# p128necontrol.net
KiCad netlist of a schematic drawn in EAGLE
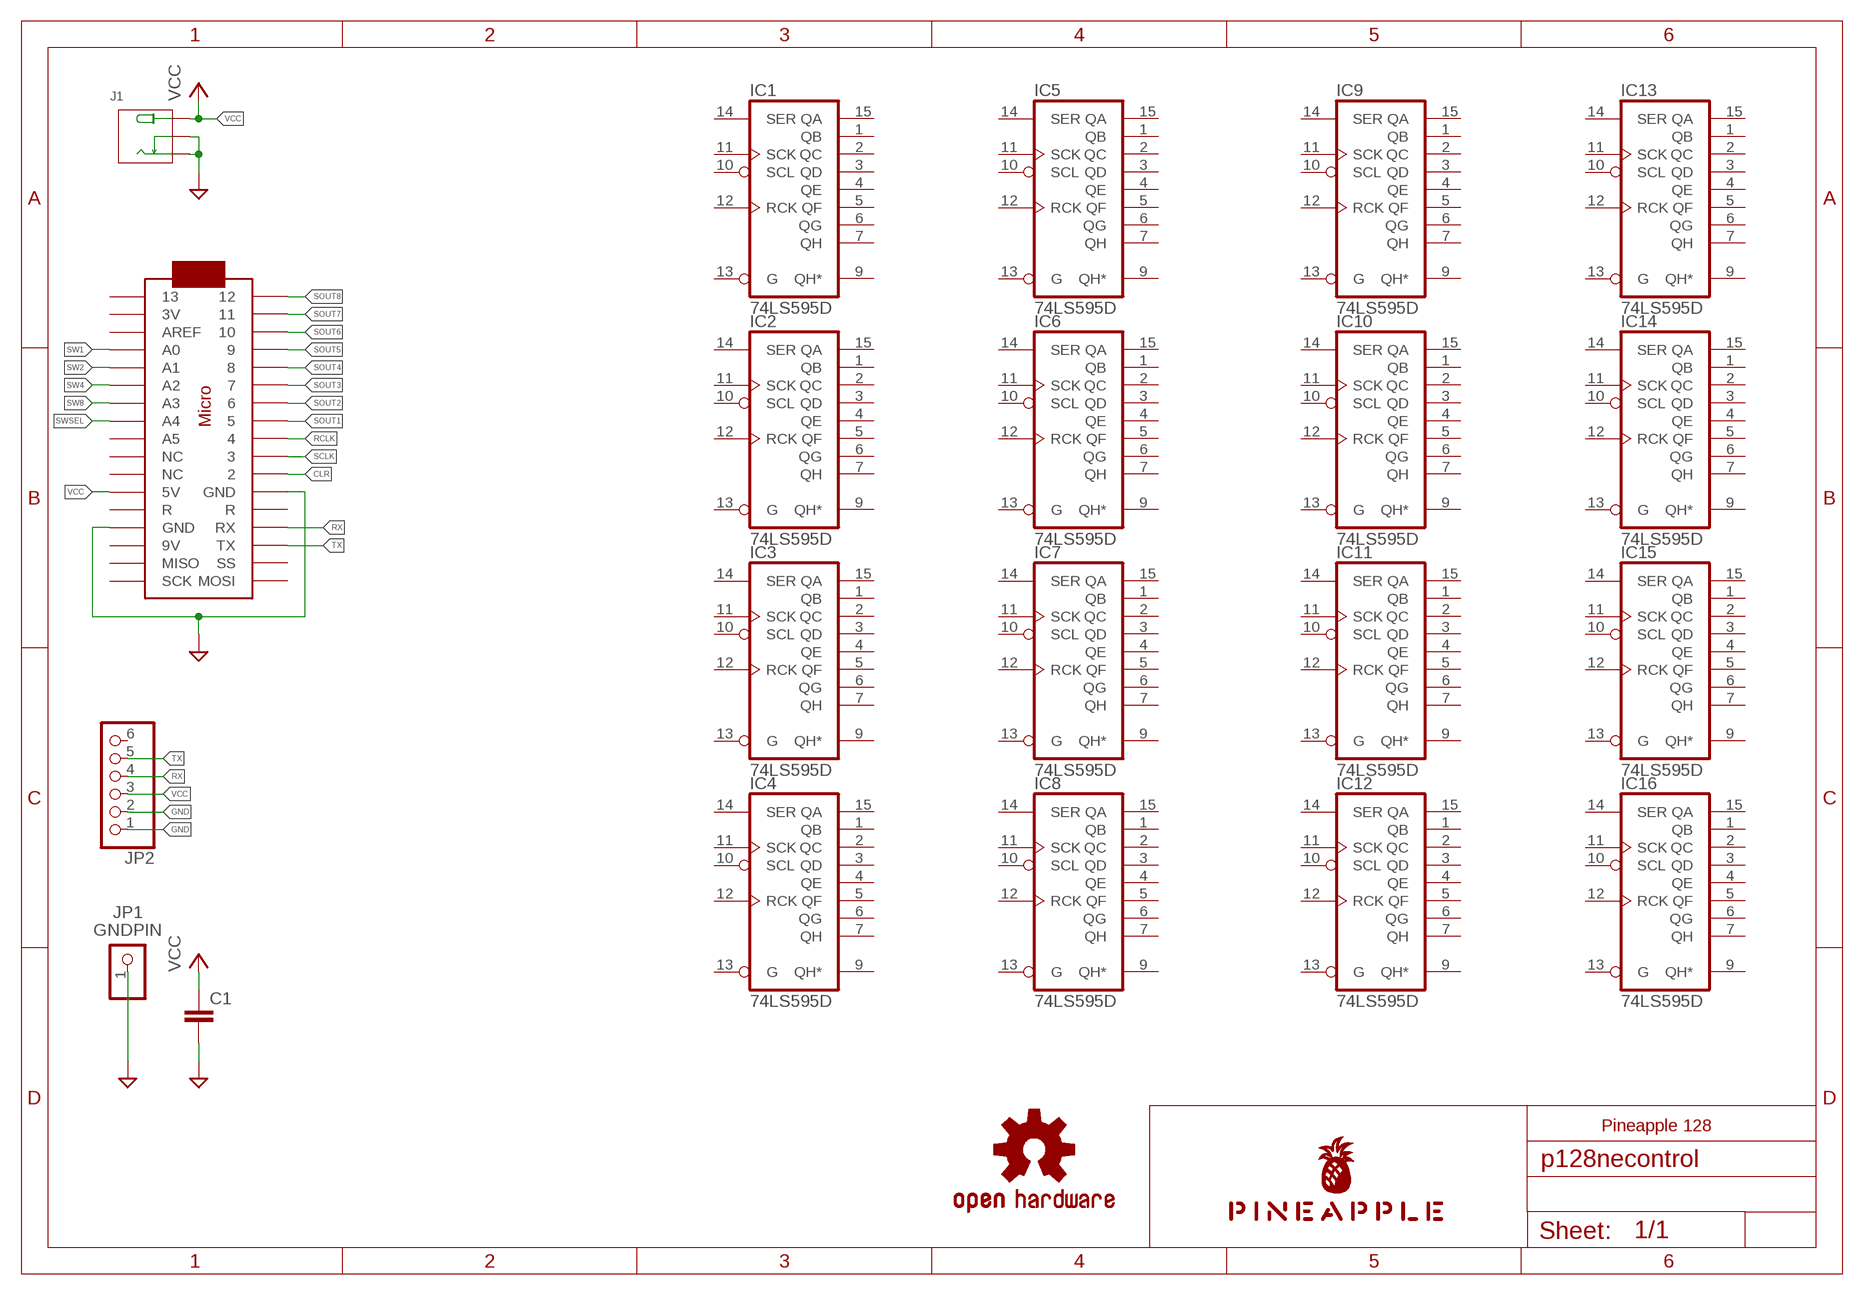
[diagram p0: schematic, sheet 1]

(export (version "E")
  (design (tool "Eeschema 10.0.6"))
  (components
    (comp (ref "C1")
      (value "C-EU025-024X044")
      (footprint "eagle-import:C025-024X044")
      (libsource (lib "eagle-import") (part "C-EU025-024X044"))
    )
    (comp (ref "IC1")
      (value "74LS595D")
      (footprint "eagle-import:SO16")
      (libsource (lib "eagle-import") (part "74595DLS"))
    )
    (comp (ref "IC2")
      (value "74LS595D")
      (footprint "eagle-import:SO16")
      (libsource (lib "eagle-import") (part "74595DLS"))
    )
    (comp (ref "IC3")
      (value "74LS595D")
      (footprint "eagle-import:SO16")
      (libsource (lib "eagle-import") (part "74595DLS"))
    )
    (comp (ref "IC4")
      (value "74LS595D")
      (footprint "eagle-import:SO16")
      (libsource (lib "eagle-import") (part "74595DLS"))
    )
    (comp (ref "IC5")
      (value "74LS595D")
      (footprint "eagle-import:SO16")
      (libsource (lib "eagle-import") (part "74595DLS"))
    )
    (comp (ref "IC6")
      (value "74LS595D")
      (footprint "eagle-import:SO16")
      (libsource (lib "eagle-import") (part "74595DLS"))
    )
    (comp (ref "IC7")
      (value "74LS595D")
      (footprint "eagle-import:SO16")
      (libsource (lib "eagle-import") (part "74595DLS"))
    )
    (comp (ref "IC8")
      (value "74LS595D")
      (footprint "eagle-import:SO16")
      (libsource (lib "eagle-import") (part "74595DLS"))
    )
    (comp (ref "IC9")
      (value "74LS595D")
      (footprint "eagle-import:SO16")
      (libsource (lib "eagle-import") (part "74595DLS"))
    )
    (comp (ref "IC10")
      (value "74LS595D")
      (footprint "eagle-import:SO16")
      (libsource (lib "eagle-import") (part "74595DLS"))
    )
    (comp (ref "IC11")
      (value "74LS595D")
      (footprint "eagle-import:SO16")
      (libsource (lib "eagle-import") (part "74595DLS"))
    )
    (comp (ref "IC12")
      (value "74LS595D")
      (footprint "eagle-import:SO16")
      (libsource (lib "eagle-import") (part "74595DLS"))
    )
    (comp (ref "IC13")
      (value "74LS595D")
      (footprint "eagle-import:SO16")
      (libsource (lib "eagle-import") (part "74595DLS"))
    )
    (comp (ref "IC14")
      (value "74LS595D")
      (footprint "eagle-import:SO16")
      (libsource (lib "eagle-import") (part "74595DLS"))
    )
    (comp (ref "IC15")
      (value "74LS595D")
      (footprint "eagle-import:SO16")
      (libsource (lib "eagle-import") (part "74595DLS"))
    )
    (comp (ref "IC16")
      (value "74LS595D")
      (footprint "eagle-import:SO16")
      (libsource (lib "eagle-import") (part "74595DLS"))
    )
    (comp (ref "J1")
      (value "JACK-DC-005'DC-005'")
      (footprint "eagle-import:3P-L14.2_W11.0_H9.0MM")
      (libsource (lib "eagle-import") (part "JACK-DC-005'DC-005'"))
    )
    (comp (ref "JP1")
      (value "GNDPIN")
      (footprint "eagle-import:1X01")
      (libsource (lib "eagle-import") (part "PINHD-1X1"))
    )
    (comp (ref "JP2")
      (value "PINHD-1X6")
      (footprint "eagle-import:1X06")
      (libsource (lib "eagle-import") (part "PINHD-1X6"))
    )
    (comp (ref "LOGO1")
      (value "OSHW-LOGOS-COPPER")
      (footprint "eagle-import:OSHW-LOGO-S_COPPER")
      (libsource (lib "eagle-import") (part "OSHW-LOGOS-COPPER"))
    )
    (comp (ref "U$1")
      (value "PINEAPPLE450_SILK")
      (footprint "eagle-import:PINEAPPLE450_SILK")
      (libsource (lib "eagle-import") (part "PINEAPPLE450_SILK"))
    )
    (comp (ref "U$2")
      (value "ARDUINOMICRO")
      (footprint "eagle-import:ARDUINOMICRO")
      (libsource (lib "eagle-import") (part "ARDUINOMICRO"))
    )
  )
  (nets
    (net (code "1") (name "CLR") (class "Default")
      (node (ref "U$2") (pin "P$11") (pinfunction "2_P$11") (pintype "bidirectional"))
    )
    (net (code "2") (name "GND") (class "Default")
      (node (ref "C1") (pin "2") (pinfunction "2_2") (pintype "passive"))
      (node (ref "J1") (pin "-1") (pinfunction "-_-1") (pintype "bidirectional"))
      (node (ref "J1") (pin "-2") (pinfunction "CDN_-2") (pintype "bidirectional"))
      (node (ref "JP1") (pin "1") (pinfunction "1_1") (pintype "passive"))
      (node (ref "JP2") (pin "1") (pinfunction "1_1") (pintype "passive"))
      (node (ref "JP2") (pin "2") (pinfunction "2_2") (pintype "passive"))
      (node (ref "U$2") (pin "P$12") (pinfunction "GND_P$12") (pintype "bidirectional"))
      (node (ref "U$2") (pin "P$21") (pinfunction "GND_P$21") (pintype "bidirectional"))
    )
    (net (code "3") (name "RCLK") (class "Default")
      (node (ref "U$2") (pin "P$9") (pinfunction "4_P$9") (pintype "bidirectional"))
    )
    (net (code "4") (name "RX") (class "Default")
      (node (ref "JP2") (pin "4") (pinfunction "4_4") (pintype "passive"))
      (node (ref "U$2") (pin "P$14") (pinfunction "RX_P$14") (pintype "bidirectional"))
    )
    (net (code "5") (name "SCLK") (class "Default")
      (node (ref "U$2") (pin "P$10") (pinfunction "3_P$10") (pintype "bidirectional"))
    )
    (net (code "6") (name "SOUT1") (class "Default")
      (node (ref "U$2") (pin "P$8") (pinfunction "5_P$8") (pintype "bidirectional"))
    )
    (net (code "7") (name "SOUT2") (class "Default")
      (node (ref "U$2") (pin "P$7") (pinfunction "6_P$7") (pintype "bidirectional"))
    )
    (net (code "8") (name "SOUT3") (class "Default")
      (node (ref "U$2") (pin "P$6") (pinfunction "7_P$6") (pintype "bidirectional"))
    )
    (net (code "9") (name "SOUT4") (class "Default")
      (node (ref "U$2") (pin "P$5") (pinfunction "8_P$5") (pintype "bidirectional"))
    )
    (net (code "10") (name "SOUT5") (class "Default")
      (node (ref "U$2") (pin "P$4") (pinfunction "9_P$4") (pintype "bidirectional"))
    )
    (net (code "11") (name "SOUT6") (class "Default")
      (node (ref "U$2") (pin "P$3") (pinfunction "10_P$3") (pintype "bidirectional"))
    )
    (net (code "12") (name "SOUT7") (class "Default")
      (node (ref "U$2") (pin "P$2") (pinfunction "11_P$2") (pintype "bidirectional"))
    )
    (net (code "13") (name "SOUT8") (class "Default")
      (node (ref "U$2") (pin "P$1") (pinfunction "12_P$1") (pintype "bidirectional"))
    )
    (net (code "14") (name "SW1") (class "Default")
      (node (ref "U$2") (pin "P$31") (pinfunction "A0_P$31") (pintype "bidirectional"))
    )
    (net (code "15") (name "SW2") (class "Default")
      (node (ref "U$2") (pin "P$30") (pinfunction "A1_P$30") (pintype "bidirectional"))
    )
    (net (code "16") (name "SW4") (class "Default")
      (node (ref "U$2") (pin "P$29") (pinfunction "A2_P$29") (pintype "bidirectional"))
    )
    (net (code "17") (name "SW8") (class "Default")
      (node (ref "U$2") (pin "P$28") (pinfunction "A3_P$28") (pintype "bidirectional"))
    )
    (net (code "18") (name "SWSEL") (class "Default")
      (node (ref "U$2") (pin "P$27") (pinfunction "A4_P$27") (pintype "bidirectional"))
    )
    (net (code "19") (name "TX") (class "Default")
      (node (ref "JP2") (pin "5") (pinfunction "5_5") (pintype "passive"))
      (node (ref "U$2") (pin "P$15") (pinfunction "TX_P$15") (pintype "bidirectional"))
    )
    (net (code "20") (name "VCC") (class "Default")
      (node (ref "C1") (pin "1") (pinfunction "1_1") (pintype "passive"))
      (node (ref "J1") (pin "+") (pinfunction "+_+") (pintype "bidirectional"))
      (node (ref "JP2") (pin "3") (pinfunction "3_3") (pintype "passive"))
      (node (ref "U$2") (pin "P$23") (pinfunction "5V_P$23") (pintype "bidirectional"))
    )
    (net (code "21") (name "unconnected-(IC1A-G-Pad13)") (class "Default")
      (node (ref "IC1") (pin "13") (pinfunction "G_13") (pintype "input"))
    )
    (net (code "22") (name "unconnected-(IC1A-QA-Pad15)") (class "Default")
      (node (ref "IC1") (pin "15") (pinfunction "QA_15") (pintype "tri_state"))
    )
    (net (code "23") (name "unconnected-(IC1A-QB-Pad1)") (class "Default")
      (node (ref "IC1") (pin "1") (pinfunction "QB_1") (pintype "tri_state"))
    )
    (net (code "24") (name "unconnected-(IC1A-QC-Pad2)") (class "Default")
      (node (ref "IC1") (pin "2") (pinfunction "QC_2") (pintype "tri_state"))
    )
    (net (code "25") (name "unconnected-(IC1A-QD-Pad3)") (class "Default")
      (node (ref "IC1") (pin "3") (pinfunction "QD_3") (pintype "tri_state"))
    )
    (net (code "26") (name "unconnected-(IC1A-QE-Pad4)") (class "Default")
      (node (ref "IC1") (pin "4") (pinfunction "QE_4") (pintype "tri_state"))
    )
    (net (code "27") (name "unconnected-(IC1A-QF-Pad5)") (class "Default")
      (node (ref "IC1") (pin "5") (pinfunction "QF_5") (pintype "tri_state"))
    )
    (net (code "28") (name "unconnected-(IC1A-QG-Pad6)") (class "Default")
      (node (ref "IC1") (pin "6") (pinfunction "QG_6") (pintype "tri_state"))
    )
    (net (code "29") (name "unconnected-(IC1A-QH*-Pad9)") (class "Default")
      (node (ref "IC1") (pin "9") (pinfunction "QH*_9") (pintype "tri_state"))
    )
    (net (code "30") (name "unconnected-(IC1A-QH-Pad7)") (class "Default")
      (node (ref "IC1") (pin "7") (pinfunction "QH_7") (pintype "tri_state"))
    )
    (net (code "31") (name "unconnected-(IC1A-RCK-Pad12)") (class "Default")
      (node (ref "IC1") (pin "12") (pinfunction "RCK_12") (pintype "input"))
    )
    (net (code "32") (name "unconnected-(IC1A-SCK-Pad11)") (class "Default")
      (node (ref "IC1") (pin "11") (pinfunction "SCK_11") (pintype "input"))
    )
    (net (code "33") (name "unconnected-(IC1A-SCL-Pad10)") (class "Default")
      (node (ref "IC1") (pin "10") (pinfunction "SCL_10") (pintype "input"))
    )
    (net (code "34") (name "unconnected-(IC1A-SER-Pad14)") (class "Default")
      (node (ref "IC1") (pin "14") (pinfunction "SER_14") (pintype "input"))
    )
    (net (code "35") (name "unconnected-(IC2A-G-Pad13)") (class "Default")
      (node (ref "IC2") (pin "13") (pinfunction "G_13") (pintype "input"))
    )
    (net (code "36") (name "unconnected-(IC2A-QA-Pad15)") (class "Default")
      (node (ref "IC2") (pin "15") (pinfunction "QA_15") (pintype "tri_state"))
    )
    (net (code "37") (name "unconnected-(IC2A-QB-Pad1)") (class "Default")
      (node (ref "IC2") (pin "1") (pinfunction "QB_1") (pintype "tri_state"))
    )
    (net (code "38") (name "unconnected-(IC2A-QC-Pad2)") (class "Default")
      (node (ref "IC2") (pin "2") (pinfunction "QC_2") (pintype "tri_state"))
    )
    (net (code "39") (name "unconnected-(IC2A-QD-Pad3)") (class "Default")
      (node (ref "IC2") (pin "3") (pinfunction "QD_3") (pintype "tri_state"))
    )
    (net (code "40") (name "unconnected-(IC2A-QE-Pad4)") (class "Default")
      (node (ref "IC2") (pin "4") (pinfunction "QE_4") (pintype "tri_state"))
    )
    (net (code "41") (name "unconnected-(IC2A-QF-Pad5)") (class "Default")
      (node (ref "IC2") (pin "5") (pinfunction "QF_5") (pintype "tri_state"))
    )
    (net (code "42") (name "unconnected-(IC2A-QG-Pad6)") (class "Default")
      (node (ref "IC2") (pin "6") (pinfunction "QG_6") (pintype "tri_state"))
    )
    (net (code "43") (name "unconnected-(IC2A-QH*-Pad9)") (class "Default")
      (node (ref "IC2") (pin "9") (pinfunction "QH*_9") (pintype "tri_state"))
    )
    (net (code "44") (name "unconnected-(IC2A-QH-Pad7)") (class "Default")
      (node (ref "IC2") (pin "7") (pinfunction "QH_7") (pintype "tri_state"))
    )
    (net (code "45") (name "unconnected-(IC2A-RCK-Pad12)") (class "Default")
      (node (ref "IC2") (pin "12") (pinfunction "RCK_12") (pintype "input"))
    )
    (net (code "46") (name "unconnected-(IC2A-SCK-Pad11)") (class "Default")
      (node (ref "IC2") (pin "11") (pinfunction "SCK_11") (pintype "input"))
    )
    (net (code "47") (name "unconnected-(IC2A-SCL-Pad10)") (class "Default")
      (node (ref "IC2") (pin "10") (pinfunction "SCL_10") (pintype "input"))
    )
    (net (code "48") (name "unconnected-(IC2A-SER-Pad14)") (class "Default")
      (node (ref "IC2") (pin "14") (pinfunction "SER_14") (pintype "input"))
    )
    (net (code "49") (name "unconnected-(IC3A-G-Pad13)") (class "Default")
      (node (ref "IC3") (pin "13") (pinfunction "G_13") (pintype "input"))
    )
    (net (code "50") (name "unconnected-(IC3A-QA-Pad15)") (class "Default")
      (node (ref "IC3") (pin "15") (pinfunction "QA_15") (pintype "tri_state"))
    )
    (net (code "51") (name "unconnected-(IC3A-QB-Pad1)") (class "Default")
      (node (ref "IC3") (pin "1") (pinfunction "QB_1") (pintype "tri_state"))
    )
    (net (code "52") (name "unconnected-(IC3A-QC-Pad2)") (class "Default")
      (node (ref "IC3") (pin "2") (pinfunction "QC_2") (pintype "tri_state"))
    )
    (net (code "53") (name "unconnected-(IC3A-QD-Pad3)") (class "Default")
      (node (ref "IC3") (pin "3") (pinfunction "QD_3") (pintype "tri_state"))
    )
    (net (code "54") (name "unconnected-(IC3A-QE-Pad4)") (class "Default")
      (node (ref "IC3") (pin "4") (pinfunction "QE_4") (pintype "tri_state"))
    )
    (net (code "55") (name "unconnected-(IC3A-QF-Pad5)") (class "Default")
      (node (ref "IC3") (pin "5") (pinfunction "QF_5") (pintype "tri_state"))
    )
    (net (code "56") (name "unconnected-(IC3A-QG-Pad6)") (class "Default")
      (node (ref "IC3") (pin "6") (pinfunction "QG_6") (pintype "tri_state"))
    )
    (net (code "57") (name "unconnected-(IC3A-QH*-Pad9)") (class "Default")
      (node (ref "IC3") (pin "9") (pinfunction "QH*_9") (pintype "tri_state"))
    )
    (net (code "58") (name "unconnected-(IC3A-QH-Pad7)") (class "Default")
      (node (ref "IC3") (pin "7") (pinfunction "QH_7") (pintype "tri_state"))
    )
    (net (code "59") (name "unconnected-(IC3A-RCK-Pad12)") (class "Default")
      (node (ref "IC3") (pin "12") (pinfunction "RCK_12") (pintype "input"))
    )
    (net (code "60") (name "unconnected-(IC3A-SCK-Pad11)") (class "Default")
      (node (ref "IC3") (pin "11") (pinfunction "SCK_11") (pintype "input"))
    )
    (net (code "61") (name "unconnected-(IC3A-SCL-Pad10)") (class "Default")
      (node (ref "IC3") (pin "10") (pinfunction "SCL_10") (pintype "input"))
    )
    (net (code "62") (name "unconnected-(IC3A-SER-Pad14)") (class "Default")
      (node (ref "IC3") (pin "14") (pinfunction "SER_14") (pintype "input"))
    )
    (net (code "63") (name "unconnected-(IC4A-G-Pad13)") (class "Default")
      (node (ref "IC4") (pin "13") (pinfunction "G_13") (pintype "input"))
    )
    (net (code "64") (name "unconnected-(IC4A-QA-Pad15)") (class "Default")
      (node (ref "IC4") (pin "15") (pinfunction "QA_15") (pintype "tri_state"))
    )
    (net (code "65") (name "unconnected-(IC4A-QB-Pad1)") (class "Default")
      (node (ref "IC4") (pin "1") (pinfunction "QB_1") (pintype "tri_state"))
    )
    (net (code "66") (name "unconnected-(IC4A-QC-Pad2)") (class "Default")
      (node (ref "IC4") (pin "2") (pinfunction "QC_2") (pintype "tri_state"))
    )
    (net (code "67") (name "unconnected-(IC4A-QD-Pad3)") (class "Default")
      (node (ref "IC4") (pin "3") (pinfunction "QD_3") (pintype "tri_state"))
    )
    (net (code "68") (name "unconnected-(IC4A-QE-Pad4)") (class "Default")
      (node (ref "IC4") (pin "4") (pinfunction "QE_4") (pintype "tri_state"))
    )
    (net (code "69") (name "unconnected-(IC4A-QF-Pad5)") (class "Default")
      (node (ref "IC4") (pin "5") (pinfunction "QF_5") (pintype "tri_state"))
    )
    (net (code "70") (name "unconnected-(IC4A-QG-Pad6)") (class "Default")
      (node (ref "IC4") (pin "6") (pinfunction "QG_6") (pintype "tri_state"))
    )
    (net (code "71") (name "unconnected-(IC4A-QH*-Pad9)") (class "Default")
      (node (ref "IC4") (pin "9") (pinfunction "QH*_9") (pintype "tri_state"))
    )
    (net (code "72") (name "unconnected-(IC4A-QH-Pad7)") (class "Default")
      (node (ref "IC4") (pin "7") (pinfunction "QH_7") (pintype "tri_state"))
    )
    (net (code "73") (name "unconnected-(IC4A-RCK-Pad12)") (class "Default")
      (node (ref "IC4") (pin "12") (pinfunction "RCK_12") (pintype "input"))
    )
    (net (code "74") (name "unconnected-(IC4A-SCK-Pad11)") (class "Default")
      (node (ref "IC4") (pin "11") (pinfunction "SCK_11") (pintype "input"))
    )
    (net (code "75") (name "unconnected-(IC4A-SCL-Pad10)") (class "Default")
      (node (ref "IC4") (pin "10") (pinfunction "SCL_10") (pintype "input"))
    )
    (net (code "76") (name "unconnected-(IC4A-SER-Pad14)") (class "Default")
      (node (ref "IC4") (pin "14") (pinfunction "SER_14") (pintype "input"))
    )
    (net (code "77") (name "unconnected-(IC5A-G-Pad13)") (class "Default")
      (node (ref "IC5") (pin "13") (pinfunction "G_13") (pintype "input"))
    )
    (net (code "78") (name "unconnected-(IC5A-QA-Pad15)") (class "Default")
      (node (ref "IC5") (pin "15") (pinfunction "QA_15") (pintype "tri_state"))
    )
    (net (code "79") (name "unconnected-(IC5A-QB-Pad1)") (class "Default")
      (node (ref "IC5") (pin "1") (pinfunction "QB_1") (pintype "tri_state"))
    )
    (net (code "80") (name "unconnected-(IC5A-QC-Pad2)") (class "Default")
      (node (ref "IC5") (pin "2") (pinfunction "QC_2") (pintype "tri_state"))
    )
    (net (code "81") (name "unconnected-(IC5A-QD-Pad3)") (class "Default")
      (node (ref "IC5") (pin "3") (pinfunction "QD_3") (pintype "tri_state"))
    )
    (net (code "82") (name "unconnected-(IC5A-QE-Pad4)") (class "Default")
      (node (ref "IC5") (pin "4") (pinfunction "QE_4") (pintype "tri_state"))
    )
    (net (code "83") (name "unconnected-(IC5A-QF-Pad5)") (class "Default")
      (node (ref "IC5") (pin "5") (pinfunction "QF_5") (pintype "tri_state"))
    )
    (net (code "84") (name "unconnected-(IC5A-QG-Pad6)") (class "Default")
      (node (ref "IC5") (pin "6") (pinfunction "QG_6") (pintype "tri_state"))
    )
    (net (code "85") (name "unconnected-(IC5A-QH*-Pad9)") (class "Default")
      (node (ref "IC5") (pin "9") (pinfunction "QH*_9") (pintype "tri_state"))
    )
    (net (code "86") (name "unconnected-(IC5A-QH-Pad7)") (class "Default")
      (node (ref "IC5") (pin "7") (pinfunction "QH_7") (pintype "tri_state"))
    )
    (net (code "87") (name "unconnected-(IC5A-RCK-Pad12)") (class "Default")
      (node (ref "IC5") (pin "12") (pinfunction "RCK_12") (pintype "input"))
    )
    (net (code "88") (name "unconnected-(IC5A-SCK-Pad11)") (class "Default")
      (node (ref "IC5") (pin "11") (pinfunction "SCK_11") (pintype "input"))
    )
    (net (code "89") (name "unconnected-(IC5A-SCL-Pad10)") (class "Default")
      (node (ref "IC5") (pin "10") (pinfunction "SCL_10") (pintype "input"))
    )
    (net (code "90") (name "unconnected-(IC5A-SER-Pad14)") (class "Default")
      (node (ref "IC5") (pin "14") (pinfunction "SER_14") (pintype "input"))
    )
    (net (code "91") (name "unconnected-(IC6A-G-Pad13)") (class "Default")
      (node (ref "IC6") (pin "13") (pinfunction "G_13") (pintype "input"))
    )
    (net (code "92") (name "unconnected-(IC6A-QA-Pad15)") (class "Default")
      (node (ref "IC6") (pin "15") (pinfunction "QA_15") (pintype "tri_state"))
    )
    (net (code "93") (name "unconnected-(IC6A-QB-Pad1)") (class "Default")
      (node (ref "IC6") (pin "1") (pinfunction "QB_1") (pintype "tri_state"))
    )
    (net (code "94") (name "unconnected-(IC6A-QC-Pad2)") (class "Default")
      (node (ref "IC6") (pin "2") (pinfunction "QC_2") (pintype "tri_state"))
    )
    (net (code "95") (name "unconnected-(IC6A-QD-Pad3)") (class "Default")
      (node (ref "IC6") (pin "3") (pinfunction "QD_3") (pintype "tri_state"))
    )
    (net (code "96") (name "unconnected-(IC6A-QE-Pad4)") (class "Default")
      (node (ref "IC6") (pin "4") (pinfunction "QE_4") (pintype "tri_state"))
    )
    (net (code "97") (name "unconnected-(IC6A-QF-Pad5)") (class "Default")
      (node (ref "IC6") (pin "5") (pinfunction "QF_5") (pintype "tri_state"))
    )
    (net (code "98") (name "unconnected-(IC6A-QG-Pad6)") (class "Default")
      (node (ref "IC6") (pin "6") (pinfunction "QG_6") (pintype "tri_state"))
    )
    (net (code "99") (name "unconnected-(IC6A-QH*-Pad9)") (class "Default")
      (node (ref "IC6") (pin "9") (pinfunction "QH*_9") (pintype "tri_state"))
    )
    (net (code "100") (name "unconnected-(IC6A-QH-Pad7)") (class "Default")
      (node (ref "IC6") (pin "7") (pinfunction "QH_7") (pintype "tri_state"))
    )
    (net (code "101") (name "unconnected-(IC6A-RCK-Pad12)") (class "Default")
      (node (ref "IC6") (pin "12") (pinfunction "RCK_12") (pintype "input"))
    )
    (net (code "102") (name "unconnected-(IC6A-SCK-Pad11)") (class "Default")
      (node (ref "IC6") (pin "11") (pinfunction "SCK_11") (pintype "input"))
    )
    (net (code "103") (name "unconnected-(IC6A-SCL-Pad10)") (class "Default")
      (node (ref "IC6") (pin "10") (pinfunction "SCL_10") (pintype "input"))
    )
    (net (code "104") (name "unconnected-(IC6A-SER-Pad14)") (class "Default")
      (node (ref "IC6") (pin "14") (pinfunction "SER_14") (pintype "input"))
    )
    (net (code "105") (name "unconnected-(IC7A-G-Pad13)") (class "Default")
      (node (ref "IC7") (pin "13") (pinfunction "G_13") (pintype "input"))
    )
    (net (code "106") (name "unconnected-(IC7A-QA-Pad15)") (class "Default")
      (node (ref "IC7") (pin "15") (pinfunction "QA_15") (pintype "tri_state"))
    )
    (net (code "107") (name "unconnected-(IC7A-QB-Pad1)") (class "Default")
      (node (ref "IC7") (pin "1") (pinfunction "QB_1") (pintype "tri_state"))
    )
    (net (code "108") (name "unconnected-(IC7A-QC-Pad2)") (class "Default")
      (node (ref "IC7") (pin "2") (pinfunction "QC_2") (pintype "tri_state"))
    )
    (net (code "109") (name "unconnected-(IC7A-QD-Pad3)") (class "Default")
      (node (ref "IC7") (pin "3") (pinfunction "QD_3") (pintype "tri_state"))
    )
    (net (code "110") (name "unconnected-(IC7A-QE-Pad4)") (class "Default")
      (node (ref "IC7") (pin "4") (pinfunction "QE_4") (pintype "tri_state"))
    )
    (net (code "111") (name "unconnected-(IC7A-QF-Pad5)") (class "Default")
      (node (ref "IC7") (pin "5") (pinfunction "QF_5") (pintype "tri_state"))
    )
    (net (code "112") (name "unconnected-(IC7A-QG-Pad6)") (class "Default")
      (node (ref "IC7") (pin "6") (pinfunction "QG_6") (pintype "tri_state"))
    )
    (net (code "113") (name "unconnected-(IC7A-QH*-Pad9)") (class "Default")
      (node (ref "IC7") (pin "9") (pinfunction "QH*_9") (pintype "tri_state"))
    )
    (net (code "114") (name "unconnected-(IC7A-QH-Pad7)") (class "Default")
      (node (ref "IC7") (pin "7") (pinfunction "QH_7") (pintype "tri_state"))
    )
    (net (code "115") (name "unconnected-(IC7A-RCK-Pad12)") (class "Default")
      (node (ref "IC7") (pin "12") (pinfunction "RCK_12") (pintype "input"))
    )
    (net (code "116") (name "unconnected-(IC7A-SCK-Pad11)") (class "Default")
      (node (ref "IC7") (pin "11") (pinfunction "SCK_11") (pintype "input"))
    )
    (net (code "117") (name "unconnected-(IC7A-SCL-Pad10)") (class "Default")
      (node (ref "IC7") (pin "10") (pinfunction "SCL_10") (pintype "input"))
    )
    (net (code "118") (name "unconnected-(IC7A-SER-Pad14)") (class "Default")
      (node (ref "IC7") (pin "14") (pinfunction "SER_14") (pintype "input"))
    )
    (net (code "119") (name "unconnected-(IC8A-G-Pad13)") (class "Default")
      (node (ref "IC8") (pin "13") (pinfunction "G_13") (pintype "input"))
    )
    (net (code "120") (name "unconnected-(IC8A-QA-Pad15)") (class "Default")
      (node (ref "IC8") (pin "15") (pinfunction "QA_15") (pintype "tri_state"))
    )
    (net (code "121") (name "unconnected-(IC8A-QB-Pad1)") (class "Default")
      (node (ref "IC8") (pin "1") (pinfunction "QB_1") (pintype "tri_state"))
    )
    (net (code "122") (name "unconnected-(IC8A-QC-Pad2)") (class "Default")
      (node (ref "IC8") (pin "2") (pinfunction "QC_2") (pintype "tri_state"))
    )
    (net (code "123") (name "unconnected-(IC8A-QD-Pad3)") (class "Default")
      (node (ref "IC8") (pin "3") (pinfunction "QD_3") (pintype "tri_state"))
    )
    (net (code "124") (name "unconnected-(IC8A-QE-Pad4)") (class "Default")
      (node (ref "IC8") (pin "4") (pinfunction "QE_4") (pintype "tri_state"))
    )
    (net (code "125") (name "unconnected-(IC8A-QF-Pad5)") (class "Default")
      (node (ref "IC8") (pin "5") (pinfunction "QF_5") (pintype "tri_state"))
    )
    (net (code "126") (name "unconnected-(IC8A-QG-Pad6)") (class "Default")
      (node (ref "IC8") (pin "6") (pinfunction "QG_6") (pintype "tri_state"))
    )
    (net (code "127") (name "unconnected-(IC8A-QH*-Pad9)") (class "Default")
      (node (ref "IC8") (pin "9") (pinfunction "QH*_9") (pintype "tri_state"))
    )
    (net (code "128") (name "unconnected-(IC8A-QH-Pad7)") (class "Default")
      (node (ref "IC8") (pin "7") (pinfunction "QH_7") (pintype "tri_state"))
    )
    (net (code "129") (name "unconnected-(IC8A-RCK-Pad12)") (class "Default")
      (node (ref "IC8") (pin "12") (pinfunction "RCK_12") (pintype "input"))
    )
    (net (code "130") (name "unconnected-(IC8A-SCK-Pad11)") (class "Default")
      (node (ref "IC8") (pin "11") (pinfunction "SCK_11") (pintype "input"))
    )
    (net (code "131") (name "unconnected-(IC8A-SCL-Pad10)") (class "Default")
      (node (ref "IC8") (pin "10") (pinfunction "SCL_10") (pintype "input"))
    )
    (net (code "132") (name "unconnected-(IC8A-SER-Pad14)") (class "Default")
      (node (ref "IC8") (pin "14") (pinfunction "SER_14") (pintype "input"))
    )
    (net (code "133") (name "unconnected-(IC9A-G-Pad13)") (class "Default")
      (node (ref "IC9") (pin "13") (pinfunction "G_13") (pintype "input"))
    )
    (net (code "134") (name "unconnected-(IC9A-QA-Pad15)") (class "Default")
      (node (ref "IC9") (pin "15") (pinfunction "QA_15") (pintype "tri_state"))
    )
    (net (code "135") (name "unconnected-(IC9A-QB-Pad1)") (class "Default")
      (node (ref "IC9") (pin "1") (pinfunction "QB_1") (pintype "tri_state"))
    )
    (net (code "136") (name "unconnected-(IC9A-QC-Pad2)") (class "Default")
      (node (ref "IC9") (pin "2") (pinfunction "QC_2") (pintype "tri_state"))
    )
    (net (code "137") (name "unconnected-(IC9A-QD-Pad3)") (class "Default")
      (node (ref "IC9") (pin "3") (pinfunction "QD_3") (pintype "tri_state"))
    )
    (net (code "138") (name "unconnected-(IC9A-QE-Pad4)") (class "Default")
      (node (ref "IC9") (pin "4") (pinfunction "QE_4") (pintype "tri_state"))
    )
    (net (code "139") (name "unconnected-(IC9A-QF-Pad5)") (class "Default")
      (node (ref "IC9") (pin "5") (pinfunction "QF_5") (pintype "tri_state"))
    )
    (net (code "140") (name "unconnected-(IC9A-QG-Pad6)") (class "Default")
      (node (ref "IC9") (pin "6") (pinfunction "QG_6") (pintype "tri_state"))
    )
    (net (code "141") (name "unconnected-(IC9A-QH*-Pad9)") (class "Default")
      (node (ref "IC9") (pin "9") (pinfunction "QH*_9") (pintype "tri_state"))
    )
    (net (code "142") (name "unconnected-(IC9A-QH-Pad7)") (class "Default")
      (node (ref "IC9") (pin "7") (pinfunction "QH_7") (pintype "tri_state"))
    )
    (net (code "143") (name "unconnected-(IC9A-RCK-Pad12)") (class "Default")
      (node (ref "IC9") (pin "12") (pinfunction "RCK_12") (pintype "input"))
    )
    (net (code "144") (name "unconnected-(IC9A-SCK-Pad11)") (class "Default")
      (node (ref "IC9") (pin "11") (pinfunction "SCK_11") (pintype "input"))
    )
    (net (code "145") (name "unconnected-(IC9A-SCL-Pad10)") (class "Default")
      (node (ref "IC9") (pin "10") (pinfunction "SCL_10") (pintype "input"))
    )
    (net (code "146") (name "unconnected-(IC9A-SER-Pad14)") (class "Default")
      (node (ref "IC9") (pin "14") (pinfunction "SER_14") (pintype "input"))
    )
    (net (code "147") (name "unconnected-(IC10A-G-Pad13)") (class "Default")
      (node (ref "IC10") (pin "13") (pinfunction "G_13") (pintype "input"))
    )
    (net (code "148") (name "unconnected-(IC10A-QA-Pad15)") (class "Default")
      (node (ref "IC10") (pin "15") (pinfunction "QA_15") (pintype "tri_state"))
    )
    (net (code "149") (name "unconnected-(IC10A-QB-Pad1)") (class "Default")
      (node (ref "IC10") (pin "1") (pinfunction "QB_1") (pintype "tri_state"))
    )
    (net (code "150") (name "unconnected-(IC10A-QC-Pad2)") (class "Default")
      (node (ref "IC10") (pin "2") (pinfunction "QC_2") (pintype "tri_state"))
    )
    (net (code "151") (name "unconnected-(IC10A-QD-Pad3)") (class "Default")
      (node (ref "IC10") (pin "3") (pinfunction "QD_3") (pintype "tri_state"))
    )
    (net (code "152") (name "unconnected-(IC10A-QE-Pad4)") (class "Default")
      (node (ref "IC10") (pin "4") (pinfunction "QE_4") (pintype "tri_state"))
    )
    (net (code "153") (name "unconnected-(IC10A-QF-Pad5)") (class "Default")
      (node (ref "IC10") (pin "5") (pinfunction "QF_5") (pintype "tri_state"))
    )
    (net (code "154") (name "unconnected-(IC10A-QG-Pad6)") (class "Default")
      (node (ref "IC10") (pin "6") (pinfunction "QG_6") (pintype "tri_state"))
    )
    (net (code "155") (name "unconnected-(IC10A-QH*-Pad9)") (class "Default")
      (node (ref "IC10") (pin "9") (pinfunction "QH*_9") (pintype "tri_state"))
    )
    (net (code "156") (name "unconnected-(IC10A-QH-Pad7)") (class "Default")
      (node (ref "IC10") (pin "7") (pinfunction "QH_7") (pintype "tri_state"))
    )
    (net (code "157") (name "unconnected-(IC10A-RCK-Pad12)") (class "Default")
      (node (ref "IC10") (pin "12") (pinfunction "RCK_12") (pintype "input"))
    )
    (net (code "158") (name "unconnected-(IC10A-SCK-Pad11)") (class "Default")
      (node (ref "IC10") (pin "11") (pinfunction "SCK_11") (pintype "input"))
    )
    (net (code "159") (name "unconnected-(IC10A-SCL-Pad10)") (class "Default")
      (node (ref "IC10") (pin "10") (pinfunction "SCL_10") (pintype "input"))
    )
    (net (code "160") (name "unconnected-(IC10A-SER-Pad14)") (class "Default")
      (node (ref "IC10") (pin "14") (pinfunction "SER_14") (pintype "input"))
    )
    (net (code "161") (name "unconnected-(IC11A-G-Pad13)") (class "Default")
      (node (ref "IC11") (pin "13") (pinfunction "G_13") (pintype "input"))
    )
    (net (code "162") (name "unconnected-(IC11A-QA-Pad15)") (class "Default")
      (node (ref "IC11") (pin "15") (pinfunction "QA_15") (pintype "tri_state"))
    )
    (net (code "163") (name "unconnected-(IC11A-QB-Pad1)") (class "Default")
      (node (ref "IC11") (pin "1") (pinfunction "QB_1") (pintype "tri_state"))
    )
    (net (code "164") (name "unconnected-(IC11A-QC-Pad2)") (class "Default")
      (node (ref "IC11") (pin "2") (pinfunction "QC_2") (pintype "tri_state"))
    )
    (net (code "165") (name "unconnected-(IC11A-QD-Pad3)") (class "Default")
      (node (ref "IC11") (pin "3") (pinfunction "QD_3") (pintype "tri_state"))
    )
    (net (code "166") (name "unconnected-(IC11A-QE-Pad4)") (class "Default")
      (node (ref "IC11") (pin "4") (pinfunction "QE_4") (pintype "tri_state"))
    )
    (net (code "167") (name "unconnected-(IC11A-QF-Pad5)") (class "Default")
      (node (ref "IC11") (pin "5") (pinfunction "QF_5") (pintype "tri_state"))
    )
    (net (code "168") (name "unconnected-(IC11A-QG-Pad6)") (class "Default")
      (node (ref "IC11") (pin "6") (pinfunction "QG_6") (pintype "tri_state"))
    )
    (net (code "169") (name "unconnected-(IC11A-QH*-Pad9)") (class "Default")
      (node (ref "IC11") (pin "9") (pinfunction "QH*_9") (pintype "tri_state"))
    )
    (net (code "170") (name "unconnected-(IC11A-QH-Pad7)") (class "Default")
      (node (ref "IC11") (pin "7") (pinfunction "QH_7") (pintype "tri_state"))
    )
    (net (code "171") (name "unconnected-(IC11A-RCK-Pad12)") (class "Default")
      (node (ref "IC11") (pin "12") (pinfunction "RCK_12") (pintype "input"))
    )
    (net (code "172") (name "unconnected-(IC11A-SCK-Pad11)") (class "Default")
      (node (ref "IC11") (pin "11") (pinfunction "SCK_11") (pintype "input"))
    )
    (net (code "173") (name "unconnected-(IC11A-SCL-Pad10)") (class "Default")
      (node (ref "IC11") (pin "10") (pinfunction "SCL_10") (pintype "input"))
    )
    (net (code "174") (name "unconnected-(IC11A-SER-Pad14)") (class "Default")
      (node (ref "IC11") (pin "14") (pinfunction "SER_14") (pintype "input"))
    )
    (net (code "175") (name "unconnected-(IC12A-G-Pad13)") (class "Default")
      (node (ref "IC12") (pin "13") (pinfunction "G_13") (pintype "input"))
    )
    (net (code "176") (name "unconnected-(IC12A-QA-Pad15)") (class "Default")
      (node (ref "IC12") (pin "15") (pinfunction "QA_15") (pintype "tri_state"))
    )
    (net (code "177") (name "unconnected-(IC12A-QB-Pad1)") (class "Default")
      (node (ref "IC12") (pin "1") (pinfunction "QB_1") (pintype "tri_state"))
    )
    (net (code "178") (name "unconnected-(IC12A-QC-Pad2)") (class "Default")
      (node (ref "IC12") (pin "2") (pinfunction "QC_2") (pintype "tri_state"))
    )
    (net (code "179") (name "unconnected-(IC12A-QD-Pad3)") (class "Default")
      (node (ref "IC12") (pin "3") (pinfunction "QD_3") (pintype "tri_state"))
    )
    (net (code "180") (name "unconnected-(IC12A-QE-Pad4)") (class "Default")
      (node (ref "IC12") (pin "4") (pinfunction "QE_4") (pintype "tri_state"))
    )
    (net (code "181") (name "unconnected-(IC12A-QF-Pad5)") (class "Default")
      (node (ref "IC12") (pin "5") (pinfunction "QF_5") (pintype "tri_state"))
    )
    (net (code "182") (name "unconnected-(IC12A-QG-Pad6)") (class "Default")
      (node (ref "IC12") (pin "6") (pinfunction "QG_6") (pintype "tri_state"))
    )
    (net (code "183") (name "unconnected-(IC12A-QH*-Pad9)") (class "Default")
      (node (ref "IC12") (pin "9") (pinfunction "QH*_9") (pintype "tri_state"))
    )
    (net (code "184") (name "unconnected-(IC12A-QH-Pad7)") (class "Default")
      (node (ref "IC12") (pin "7") (pinfunction "QH_7") (pintype "tri_state"))
    )
    (net (code "185") (name "unconnected-(IC12A-RCK-Pad12)") (class "Default")
      (node (ref "IC12") (pin "12") (pinfunction "RCK_12") (pintype "input"))
    )
    (net (code "186") (name "unconnected-(IC12A-SCK-Pad11)") (class "Default")
      (node (ref "IC12") (pin "11") (pinfunction "SCK_11") (pintype "input"))
    )
    (net (code "187") (name "unconnected-(IC12A-SCL-Pad10)") (class "Default")
      (node (ref "IC12") (pin "10") (pinfunction "SCL_10") (pintype "input"))
    )
    (net (code "188") (name "unconnected-(IC12A-SER-Pad14)") (class "Default")
      (node (ref "IC12") (pin "14") (pinfunction "SER_14") (pintype "input"))
    )
    (net (code "189") (name "unconnected-(IC13A-G-Pad13)") (class "Default")
      (node (ref "IC13") (pin "13") (pinfunction "G_13") (pintype "input"))
    )
    (net (code "190") (name "unconnected-(IC13A-QA-Pad15)") (class "Default")
      (node (ref "IC13") (pin "15") (pinfunction "QA_15") (pintype "tri_state"))
    )
    (net (code "191") (name "unconnected-(IC13A-QB-Pad1)") (class "Default")
      (node (ref "IC13") (pin "1") (pinfunction "QB_1") (pintype "tri_state"))
    )
    (net (code "192") (name "unconnected-(IC13A-QC-Pad2)") (class "Default")
      (node (ref "IC13") (pin "2") (pinfunction "QC_2") (pintype "tri_state"))
    )
    (net (code "193") (name "unconnected-(IC13A-QD-Pad3)") (class "Default")
      (node (ref "IC13") (pin "3") (pinfunction "QD_3") (pintype "tri_state"))
    )
    (net (code "194") (name "unconnected-(IC13A-QE-Pad4)") (class "Default")
      (node (ref "IC13") (pin "4") (pinfunction "QE_4") (pintype "tri_state"))
    )
    (net (code "195") (name "unconnected-(IC13A-QF-Pad5)") (class "Default")
      (node (ref "IC13") (pin "5") (pinfunction "QF_5") (pintype "tri_state"))
    )
    (net (code "196") (name "unconnected-(IC13A-QG-Pad6)") (class "Default")
      (node (ref "IC13") (pin "6") (pinfunction "QG_6") (pintype "tri_state"))
    )
    (net (code "197") (name "unconnected-(IC13A-QH*-Pad9)") (class "Default")
      (node (ref "IC13") (pin "9") (pinfunction "QH*_9") (pintype "tri_state"))
    )
    (net (code "198") (name "unconnected-(IC13A-QH-Pad7)") (class "Default")
      (node (ref "IC13") (pin "7") (pinfunction "QH_7") (pintype "tri_state"))
    )
    (net (code "199") (name "unconnected-(IC13A-RCK-Pad12)") (class "Default")
      (node (ref "IC13") (pin "12") (pinfunction "RCK_12") (pintype "input"))
    )
    (net (code "200") (name "unconnected-(IC13A-SCK-Pad11)") (class "Default")
      (node (ref "IC13") (pin "11") (pinfunction "SCK_11") (pintype "input"))
    )
    (net (code "201") (name "unconnected-(IC13A-SCL-Pad10)") (class "Default")
      (node (ref "IC13") (pin "10") (pinfunction "SCL_10") (pintype "input"))
    )
    (net (code "202") (name "unconnected-(IC13A-SER-Pad14)") (class "Default")
      (node (ref "IC13") (pin "14") (pinfunction "SER_14") (pintype "input"))
    )
    (net (code "203") (name "unconnected-(IC14A-G-Pad13)") (class "Default")
      (node (ref "IC14") (pin "13") (pinfunction "G_13") (pintype "input"))
    )
    (net (code "204") (name "unconnected-(IC14A-QA-Pad15)") (class "Default")
      (node (ref "IC14") (pin "15") (pinfunction "QA_15") (pintype "tri_state"))
    )
    (net (code "205") (name "unconnected-(IC14A-QB-Pad1)") (class "Default")
      (node (ref "IC14") (pin "1") (pinfunction "QB_1") (pintype "tri_state"))
    )
    (net (code "206") (name "unconnected-(IC14A-QC-Pad2)") (class "Default")
      (node (ref "IC14") (pin "2") (pinfunction "QC_2") (pintype "tri_state"))
    )
    (net (code "207") (name "unconnected-(IC14A-QD-Pad3)") (class "Default")
      (node (ref "IC14") (pin "3") (pinfunction "QD_3") (pintype "tri_state"))
    )
    (net (code "208") (name "unconnected-(IC14A-QE-Pad4)") (class "Default")
      (node (ref "IC14") (pin "4") (pinfunction "QE_4") (pintype "tri_state"))
    )
    (net (code "209") (name "unconnected-(IC14A-QF-Pad5)") (class "Default")
      (node (ref "IC14") (pin "5") (pinfunction "QF_5") (pintype "tri_state"))
    )
    (net (code "210") (name "unconnected-(IC14A-QG-Pad6)") (class "Default")
      (node (ref "IC14") (pin "6") (pinfunction "QG_6") (pintype "tri_state"))
    )
    (net (code "211") (name "unconnected-(IC14A-QH*-Pad9)") (class "Default")
      (node (ref "IC14") (pin "9") (pinfunction "QH*_9") (pintype "tri_state"))
    )
    (net (code "212") (name "unconnected-(IC14A-QH-Pad7)") (class "Default")
      (node (ref "IC14") (pin "7") (pinfunction "QH_7") (pintype "tri_state"))
    )
    (net (code "213") (name "unconnected-(IC14A-RCK-Pad12)") (class "Default")
      (node (ref "IC14") (pin "12") (pinfunction "RCK_12") (pintype "input"))
    )
    (net (code "214") (name "unconnected-(IC14A-SCK-Pad11)") (class "Default")
      (node (ref "IC14") (pin "11") (pinfunction "SCK_11") (pintype "input"))
    )
    (net (code "215") (name "unconnected-(IC14A-SCL-Pad10)") (class "Default")
      (node (ref "IC14") (pin "10") (pinfunction "SCL_10") (pintype "input"))
    )
    (net (code "216") (name "unconnected-(IC14A-SER-Pad14)") (class "Default")
      (node (ref "IC14") (pin "14") (pinfunction "SER_14") (pintype "input"))
    )
    (net (code "217") (name "unconnected-(IC15A-G-Pad13)") (class "Default")
      (node (ref "IC15") (pin "13") (pinfunction "G_13") (pintype "input"))
    )
    (net (code "218") (name "unconnected-(IC15A-QA-Pad15)") (class "Default")
      (node (ref "IC15") (pin "15") (pinfunction "QA_15") (pintype "tri_state"))
    )
    (net (code "219") (name "unconnected-(IC15A-QB-Pad1)") (class "Default")
      (node (ref "IC15") (pin "1") (pinfunction "QB_1") (pintype "tri_state"))
    )
    (net (code "220") (name "unconnected-(IC15A-QC-Pad2)") (class "Default")
      (node (ref "IC15") (pin "2") (pinfunction "QC_2") (pintype "tri_state"))
    )
    (net (code "221") (name "unconnected-(IC15A-QD-Pad3)") (class "Default")
      (node (ref "IC15") (pin "3") (pinfunction "QD_3") (pintype "tri_state"))
    )
    (net (code "222") (name "unconnected-(IC15A-QE-Pad4)") (class "Default")
      (node (ref "IC15") (pin "4") (pinfunction "QE_4") (pintype "tri_state"))
    )
    (net (code "223") (name "unconnected-(IC15A-QF-Pad5)") (class "Default")
      (node (ref "IC15") (pin "5") (pinfunction "QF_5") (pintype "tri_state"))
    )
    (net (code "224") (name "unconnected-(IC15A-QG-Pad6)") (class "Default")
      (node (ref "IC15") (pin "6") (pinfunction "QG_6") (pintype "tri_state"))
    )
    (net (code "225") (name "unconnected-(IC15A-QH*-Pad9)") (class "Default")
      (node (ref "IC15") (pin "9") (pinfunction "QH*_9") (pintype "tri_state"))
    )
    (net (code "226") (name "unconnected-(IC15A-QH-Pad7)") (class "Default")
      (node (ref "IC15") (pin "7") (pinfunction "QH_7") (pintype "tri_state"))
    )
    (net (code "227") (name "unconnected-(IC15A-RCK-Pad12)") (class "Default")
      (node (ref "IC15") (pin "12") (pinfunction "RCK_12") (pintype "input"))
    )
    (net (code "228") (name "unconnected-(IC15A-SCK-Pad11)") (class "Default")
      (node (ref "IC15") (pin "11") (pinfunction "SCK_11") (pintype "input"))
    )
    (net (code "229") (name "unconnected-(IC15A-SCL-Pad10)") (class "Default")
      (node (ref "IC15") (pin "10") (pinfunction "SCL_10") (pintype "input"))
    )
    (net (code "230") (name "unconnected-(IC15A-SER-Pad14)") (class "Default")
      (node (ref "IC15") (pin "14") (pinfunction "SER_14") (pintype "input"))
    )
    (net (code "231") (name "unconnected-(IC16A-G-Pad13)") (class "Default")
      (node (ref "IC16") (pin "13") (pinfunction "G_13") (pintype "input"))
    )
    (net (code "232") (name "unconnected-(IC16A-QA-Pad15)") (class "Default")
      (node (ref "IC16") (pin "15") (pinfunction "QA_15") (pintype "tri_state"))
    )
    (net (code "233") (name "unconnected-(IC16A-QB-Pad1)") (class "Default")
      (node (ref "IC16") (pin "1") (pinfunction "QB_1") (pintype "tri_state"))
    )
    (net (code "234") (name "unconnected-(IC16A-QC-Pad2)") (class "Default")
      (node (ref "IC16") (pin "2") (pinfunction "QC_2") (pintype "tri_state"))
    )
    (net (code "235") (name "unconnected-(IC16A-QD-Pad3)") (class "Default")
      (node (ref "IC16") (pin "3") (pinfunction "QD_3") (pintype "tri_state"))
    )
    (net (code "236") (name "unconnected-(IC16A-QE-Pad4)") (class "Default")
      (node (ref "IC16") (pin "4") (pinfunction "QE_4") (pintype "tri_state"))
    )
    (net (code "237") (name "unconnected-(IC16A-QF-Pad5)") (class "Default")
      (node (ref "IC16") (pin "5") (pinfunction "QF_5") (pintype "tri_state"))
    )
    (net (code "238") (name "unconnected-(IC16A-QG-Pad6)") (class "Default")
      (node (ref "IC16") (pin "6") (pinfunction "QG_6") (pintype "tri_state"))
    )
    (net (code "239") (name "unconnected-(IC16A-QH*-Pad9)") (class "Default")
      (node (ref "IC16") (pin "9") (pinfunction "QH*_9") (pintype "tri_state"))
    )
    (net (code "240") (name "unconnected-(IC16A-QH-Pad7)") (class "Default")
      (node (ref "IC16") (pin "7") (pinfunction "QH_7") (pintype "tri_state"))
    )
    (net (code "241") (name "unconnected-(IC16A-RCK-Pad12)") (class "Default")
      (node (ref "IC16") (pin "12") (pinfunction "RCK_12") (pintype "input"))
    )
    (net (code "242") (name "unconnected-(IC16A-SCK-Pad11)") (class "Default")
      (node (ref "IC16") (pin "11") (pinfunction "SCK_11") (pintype "input"))
    )
    (net (code "243") (name "unconnected-(IC16A-SCL-Pad10)") (class "Default")
      (node (ref "IC16") (pin "10") (pinfunction "SCL_10") (pintype "input"))
    )
    (net (code "244") (name "unconnected-(IC16A-SER-Pad14)") (class "Default")
      (node (ref "IC16") (pin "14") (pinfunction "SER_14") (pintype "input"))
    )
    (net (code "245") (name "unconnected-(JP2-Pad6)") (class "Default")
      (node (ref "JP2") (pin "6") (pinfunction "6_6") (pintype "passive"))
    )
    (net (code "246") (name "unconnected-(U$2-3V-PadP$33)") (class "Default")
      (node (ref "U$2") (pin "P$33") (pinfunction "3V_P$33") (pintype "bidirectional"))
    )
    (net (code "247") (name "unconnected-(U$2-9V-PadP$20)") (class "Default")
      (node (ref "U$2") (pin "P$20") (pinfunction "9V_P$20") (pintype "bidirectional"))
    )
    (net (code "248") (name "unconnected-(U$2-13-PadP$34)") (class "Default")
      (node (ref "U$2") (pin "P$34") (pinfunction "13_P$34") (pintype "bidirectional"))
    )
    (net (code "249") (name "unconnected-(U$2-A5-PadP$26)") (class "Default")
      (node (ref "U$2") (pin "P$26") (pinfunction "A5_P$26") (pintype "bidirectional"))
    )
    (net (code "250") (name "unconnected-(U$2-AREF-PadP$32)") (class "Default")
      (node (ref "U$2") (pin "P$32") (pinfunction "AREF_P$32") (pintype "bidirectional"))
    )
    (net (code "251") (name "unconnected-(U$2-MISO-PadP$19)") (class "Default")
      (node (ref "U$2") (pin "P$19") (pinfunction "MISO_P$19") (pintype "bidirectional"))
    )
    (net (code "252") (name "unconnected-(U$2-MOSI-PadP$17)") (class "Default")
      (node (ref "U$2") (pin "P$17") (pinfunction "MOSI_P$17") (pintype "bidirectional"))
    )
    (net (code "253") (name "unconnected-(U$2-NC-PadP$24)") (class "Default")
      (node (ref "U$2") (pin "P$24") (pinfunction "NC_P$24") (pintype "bidirectional"))
    )
    (net (code "254") (name "unconnected-(U$2-NC-PadP$25)") (class "Default")
      (node (ref "U$2") (pin "P$25") (pinfunction "NC_P$25") (pintype "bidirectional"))
    )
    (net (code "255") (name "unconnected-(U$2-R-PadP$13)") (class "Default")
      (node (ref "U$2") (pin "P$13") (pinfunction "R_P$13") (pintype "bidirectional"))
    )
    (net (code "256") (name "unconnected-(U$2-R-PadP$22)") (class "Default")
      (node (ref "U$2") (pin "P$22") (pinfunction "R_P$22") (pintype "bidirectional"))
    )
    (net (code "257") (name "unconnected-(U$2-SCK-PadP$18)") (class "Default")
      (node (ref "U$2") (pin "P$18") (pinfunction "SCK_P$18") (pintype "bidirectional"))
    )
    (net (code "258") (name "unconnected-(U$2-SS-PadP$16)") (class "Default")
      (node (ref "U$2") (pin "P$16") (pinfunction "SS_P$16") (pintype "bidirectional"))
    )
  )
)
